# mboard.net
KiCad netlist of a schematic drawn in Altium Designer
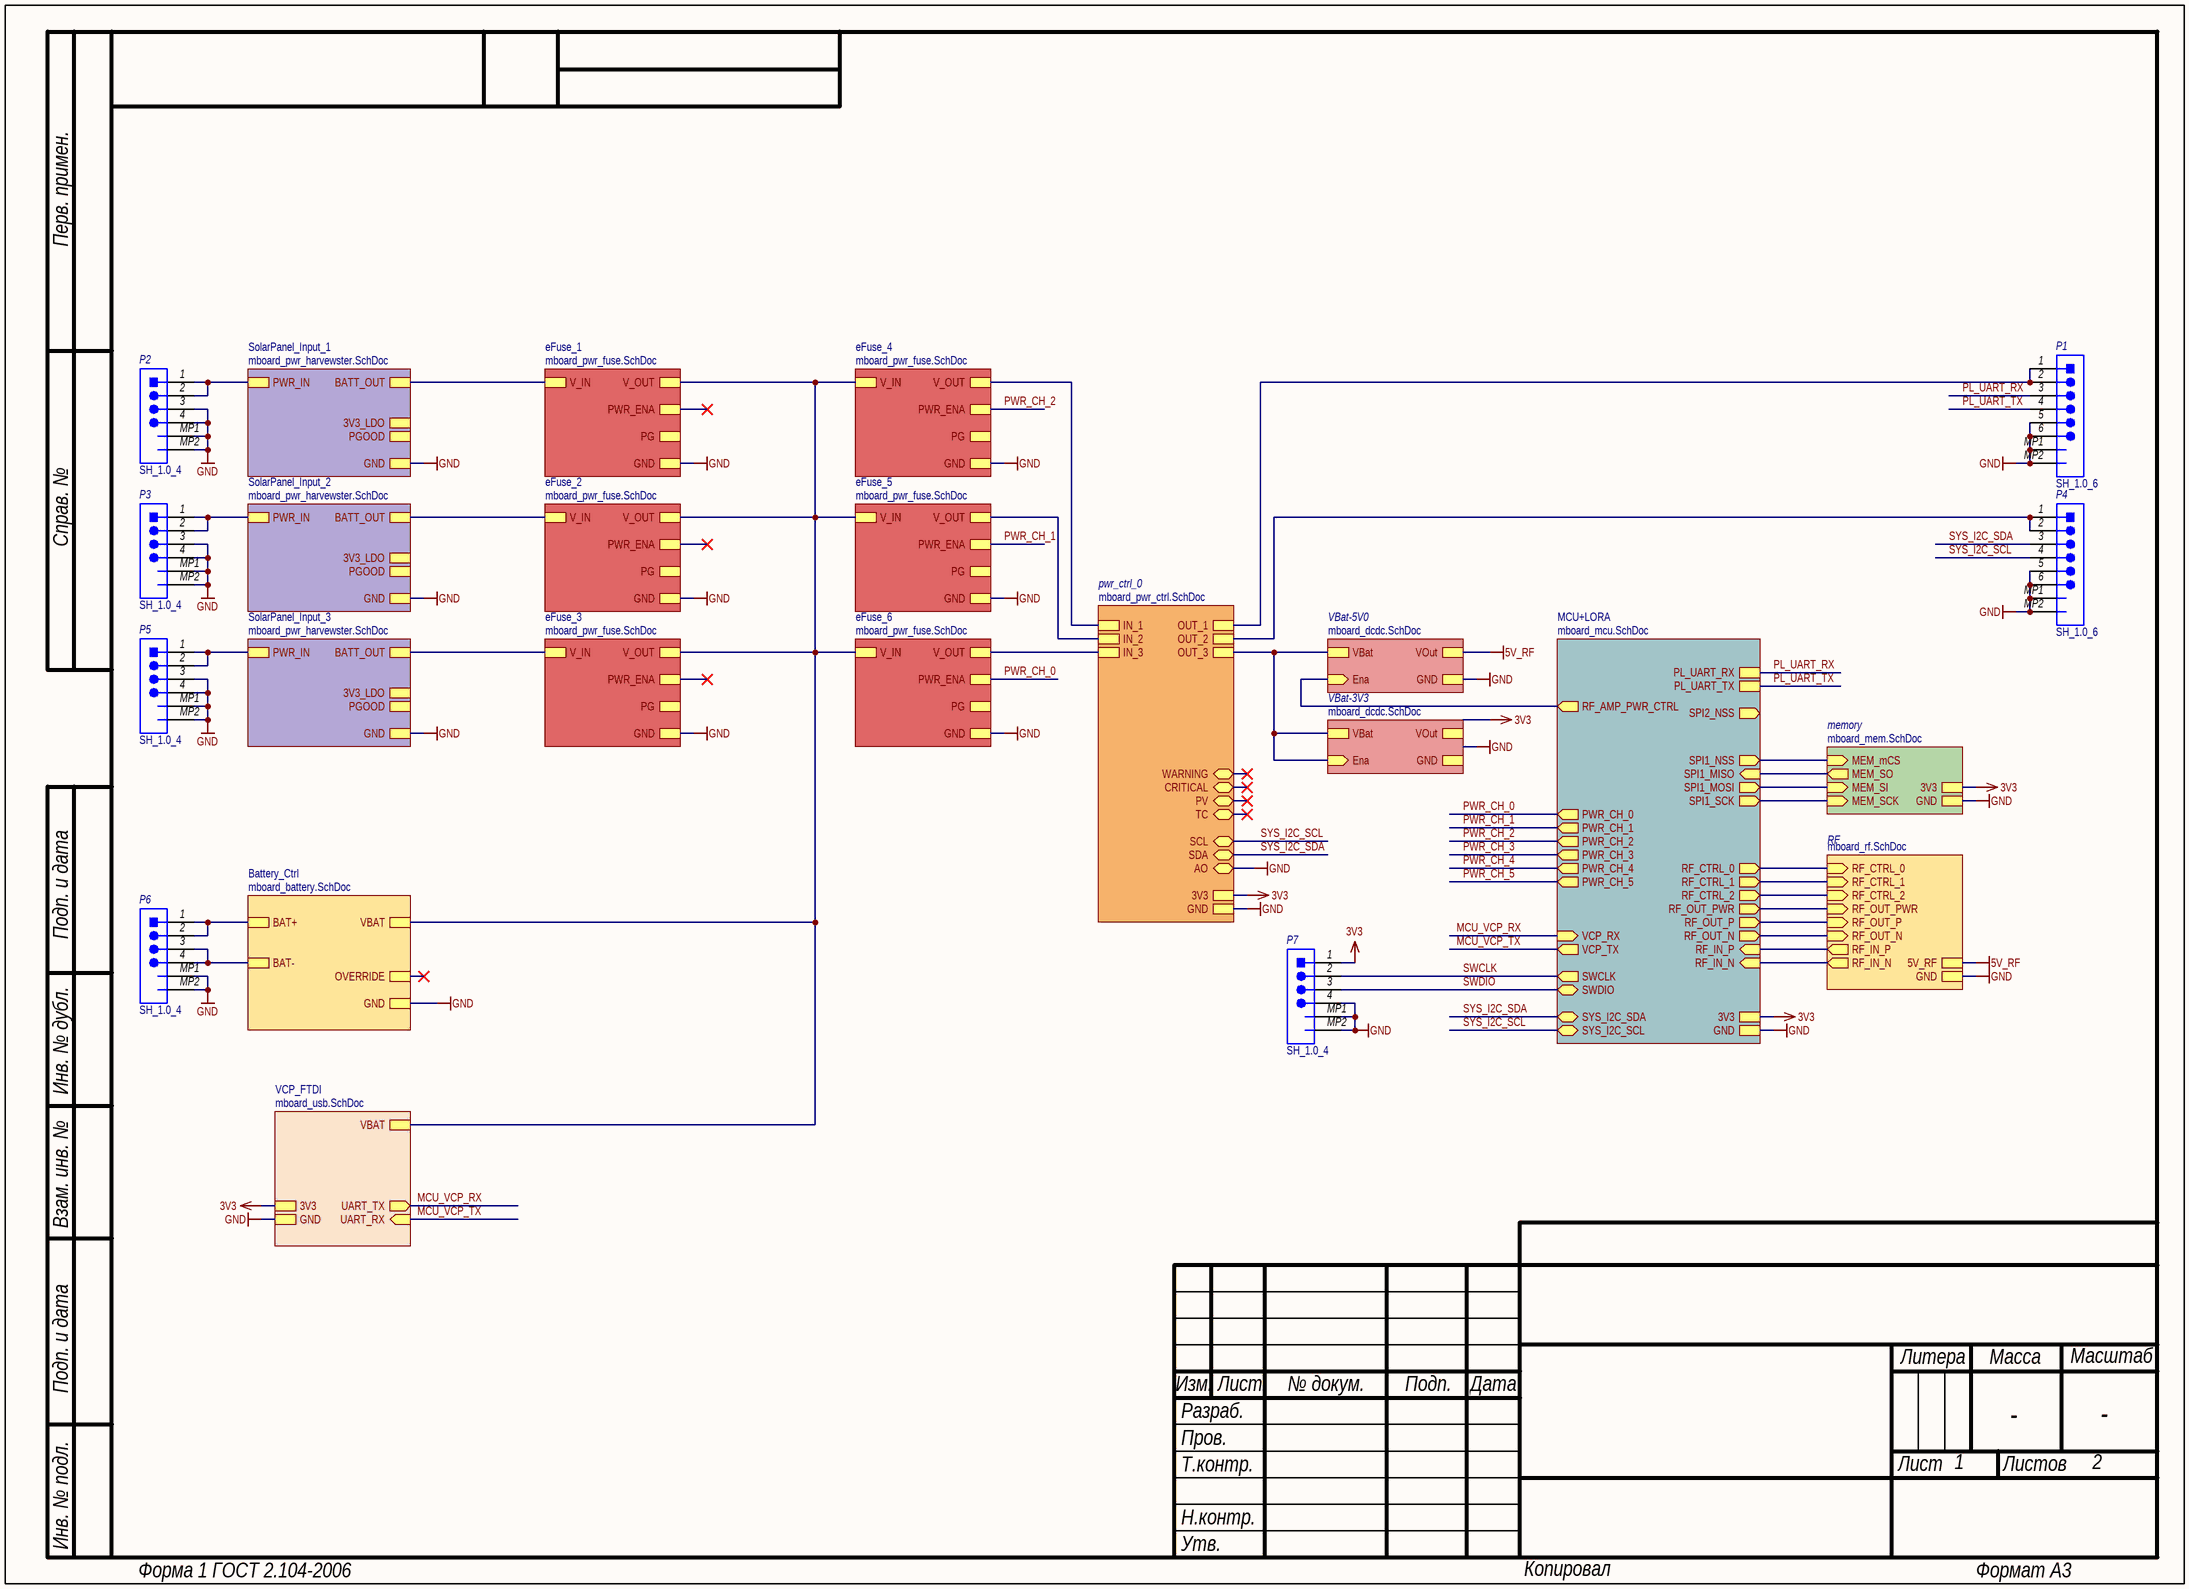
[diagram p0: mboard.SchDoc]

(export (version "E")
  (design (tool "Eeschema 10.0.6"))
  (components
    (comp (ref "P1")
      (value "SH_1.0_6")
      (footprint "SH_1.0_6")
      (description "JST SH1.0, 1.0 mm pitch/Disconnactable crimp style connectors")
      (fields (field (name "НАИМЕНОВАНИЕ") "SH_1.0_6"))
      (libsource (lib "Connector") (part "SH_1.0_6"))
    )
    (comp (ref "P2")
      (value "SH_1.0_4")
      (footprint "SH_1.0_6")
      (description "JST SH1.0, 1.0 mm pitch/Disconnactable crimp style connectors")
      (fields (field (name "НАИМЕНОВАНИЕ") "SH_1.0_4"))
      (libsource (lib "Connector") (part "SH_1.0_4"))
    )
    (comp (ref "P3")
      (value "SH_1.0_4")
      (footprint "SH_1.0_6")
      (description "JST SH1.0, 1.0 mm pitch/Disconnactable crimp style connectors")
      (fields (field (name "НАИМЕНОВАНИЕ") "SH_1.0_4"))
      (libsource (lib "Connector") (part "SH_1.0_4"))
    )
    (comp (ref "P4")
      (value "SH_1.0_6")
      (footprint "SH_1.0_6")
      (description "JST SH1.0, 1.0 mm pitch/Disconnactable crimp style connectors")
      (fields (field (name "НАИМЕНОВАНИЕ") "SH_1.0_6"))
      (libsource (lib "Connector") (part "SH_1.0_6"))
    )
    (comp (ref "P5")
      (value "SH_1.0_4")
      (footprint "SH_1.0_6")
      (description "JST SH1.0, 1.0 mm pitch/Disconnactable crimp style connectors")
      (fields (field (name "НАИМЕНОВАНИЕ") "SH_1.0_4"))
      (libsource (lib "Connector") (part "SH_1.0_4"))
    )
    (comp (ref "P6")
      (value "SH_1.0_4")
      (footprint "SH_1.0_6")
      (description "JST SH1.0, 1.0 mm pitch/Disconnactable crimp style connectors")
      (fields (field (name "НАИМЕНОВАНИЕ") "SH_1.0_4"))
      (libsource (lib "Connector") (part "SH_1.0_4"))
    )
    (comp (ref "P7")
      (value "SH_1.0_4")
      (footprint "SH_1.0_6")
      (description "JST SH1.0, 1.0 mm pitch/Disconnactable crimp style connectors")
      (fields (field (name "НАИМЕНОВАНИЕ") "SH_1.0_4"))
      (libsource (lib "Connector") (part "SH_1.0_4"))
    )
  )
  (nets
    (net (code "4") (name "/BAT+") (class "Default")
      (node (ref "P6") (pin "1") (pinfunction "1_1") (pintype "passive"))
      (node (ref "P6") (pin "2") (pinfunction "2_2") (pintype "passive"))
    )
    (net (code "5") (name "/BAT-") (class "Default")
      (node (ref "P6") (pin "3") (pinfunction "3_3") (pintype "passive"))
      (node (ref "P6") (pin "4") (pinfunction "4_4") (pintype "passive"))
    )
    (net (code "18") (name "/OUT_1") (class "Default")
      (node (ref "P1") (pin "1") (pinfunction "1_1") (pintype "passive"))
      (node (ref "P1") (pin "2") (pinfunction "2_2") (pintype "passive"))
    )
    (net (code "19") (name "/OUT_2") (class "Default")
      (node (ref "P4") (pin "1") (pinfunction "1_1") (pintype "passive"))
      (node (ref "P4") (pin "2") (pinfunction "2_2") (pintype "passive"))
    )
    (net (code "30") (name "/PL_UART_RX") (class "Default")
      (node (ref "P1") (pin "3") (pinfunction "3_3") (pintype "passive"))
    )
    (net (code "31") (name "/PL_UART_TX") (class "Default")
      (node (ref "P1") (pin "4") (pinfunction "4_4") (pintype "passive"))
    )
    (net (code "42") (name "/PWR_IN") (class "Default")
      (node (ref "P5") (pin "1") (pinfunction "1_1") (pintype "passive"))
      (node (ref "P5") (pin "2") (pinfunction "2_2") (pintype "passive"))
    )
    (net (code "43") (name "/PWR_IN_1") (class "Default")
      (node (ref "P2") (pin "1") (pinfunction "1_1") (pintype "passive"))
      (node (ref "P2") (pin "2") (pinfunction "2_2") (pintype "passive"))
    )
    (net (code "44") (name "/PWR_IN_2") (class "Default")
      (node (ref "P3") (pin "1") (pinfunction "1_1") (pintype "passive"))
      (node (ref "P3") (pin "2") (pinfunction "2_2") (pintype "passive"))
    )
    (net (code "58") (name "/SWCLK") (class "Default")
      (node (ref "P7") (pin "2") (pinfunction "2_2") (pintype "passive"))
    )
    (net (code "59") (name "/SWDIO") (class "Default")
      (node (ref "P7") (pin "3") (pinfunction "3_3") (pintype "passive"))
    )
    (net (code "60") (name "/SYS_I2C_SCL") (class "Default")
      (node (ref "P4") (pin "4") (pinfunction "4_4") (pintype "passive"))
    )
    (net (code "61") (name "/SYS_I2C_SDA") (class "Default")
      (node (ref "P4") (pin "3") (pinfunction "3_3") (pintype "passive"))
    )
    (net (code "66") (name "3V3") (class "Default")
      (node (ref "P7") (pin "1") (pinfunction "1_1") (pintype "passive"))
    )
    (net (code "68") (name "GND") (class "Default")
      (node (ref "P1") (pin "5") (pinfunction "5_5") (pintype "passive"))
      (node (ref "P1") (pin "6") (pinfunction "6_6") (pintype "passive"))
      (node (ref "P1") (pin "MP1") (pinfunction "MP1_MP1") (pintype "passive"))
      (node (ref "P1") (pin "MP2") (pinfunction "MP2_MP2") (pintype "passive"))
      (node (ref "P2") (pin "3") (pinfunction "3_3") (pintype "passive"))
      (node (ref "P2") (pin "4") (pinfunction "4_4") (pintype "passive"))
      (node (ref "P2") (pin "MP1") (pinfunction "MP1_MP1") (pintype "passive"))
      (node (ref "P2") (pin "MP2") (pinfunction "MP2_MP2") (pintype "passive"))
      (node (ref "P3") (pin "3") (pinfunction "3_3") (pintype "passive"))
      (node (ref "P3") (pin "4") (pinfunction "4_4") (pintype "passive"))
      (node (ref "P3") (pin "MP1") (pinfunction "MP1_MP1") (pintype "passive"))
      (node (ref "P3") (pin "MP2") (pinfunction "MP2_MP2") (pintype "passive"))
      (node (ref "P4") (pin "5") (pinfunction "5_5") (pintype "passive"))
      (node (ref "P4") (pin "6") (pinfunction "6_6") (pintype "passive"))
      (node (ref "P4") (pin "MP1") (pinfunction "MP1_MP1") (pintype "passive"))
      (node (ref "P4") (pin "MP2") (pinfunction "MP2_MP2") (pintype "passive"))
      (node (ref "P5") (pin "3") (pinfunction "3_3") (pintype "passive"))
      (node (ref "P5") (pin "4") (pinfunction "4_4") (pintype "passive"))
      (node (ref "P5") (pin "MP1") (pinfunction "MP1_MP1") (pintype "passive"))
      (node (ref "P5") (pin "MP2") (pinfunction "MP2_MP2") (pintype "passive"))
      (node (ref "P6") (pin "MP1") (pinfunction "MP1_MP1") (pintype "passive"))
      (node (ref "P6") (pin "MP2") (pinfunction "MP2_MP2") (pintype "passive"))
      (node (ref "P7") (pin "4") (pinfunction "4_4") (pintype "passive"))
      (node (ref "P7") (pin "MP1") (pinfunction "MP1_MP1") (pintype "passive"))
      (node (ref "P7") (pin "MP2") (pinfunction "MP2_MP2") (pintype "passive"))
    )
  )
)
